# KOTLETA.net
KiCad netlist of a schematic drawn in EAGLE
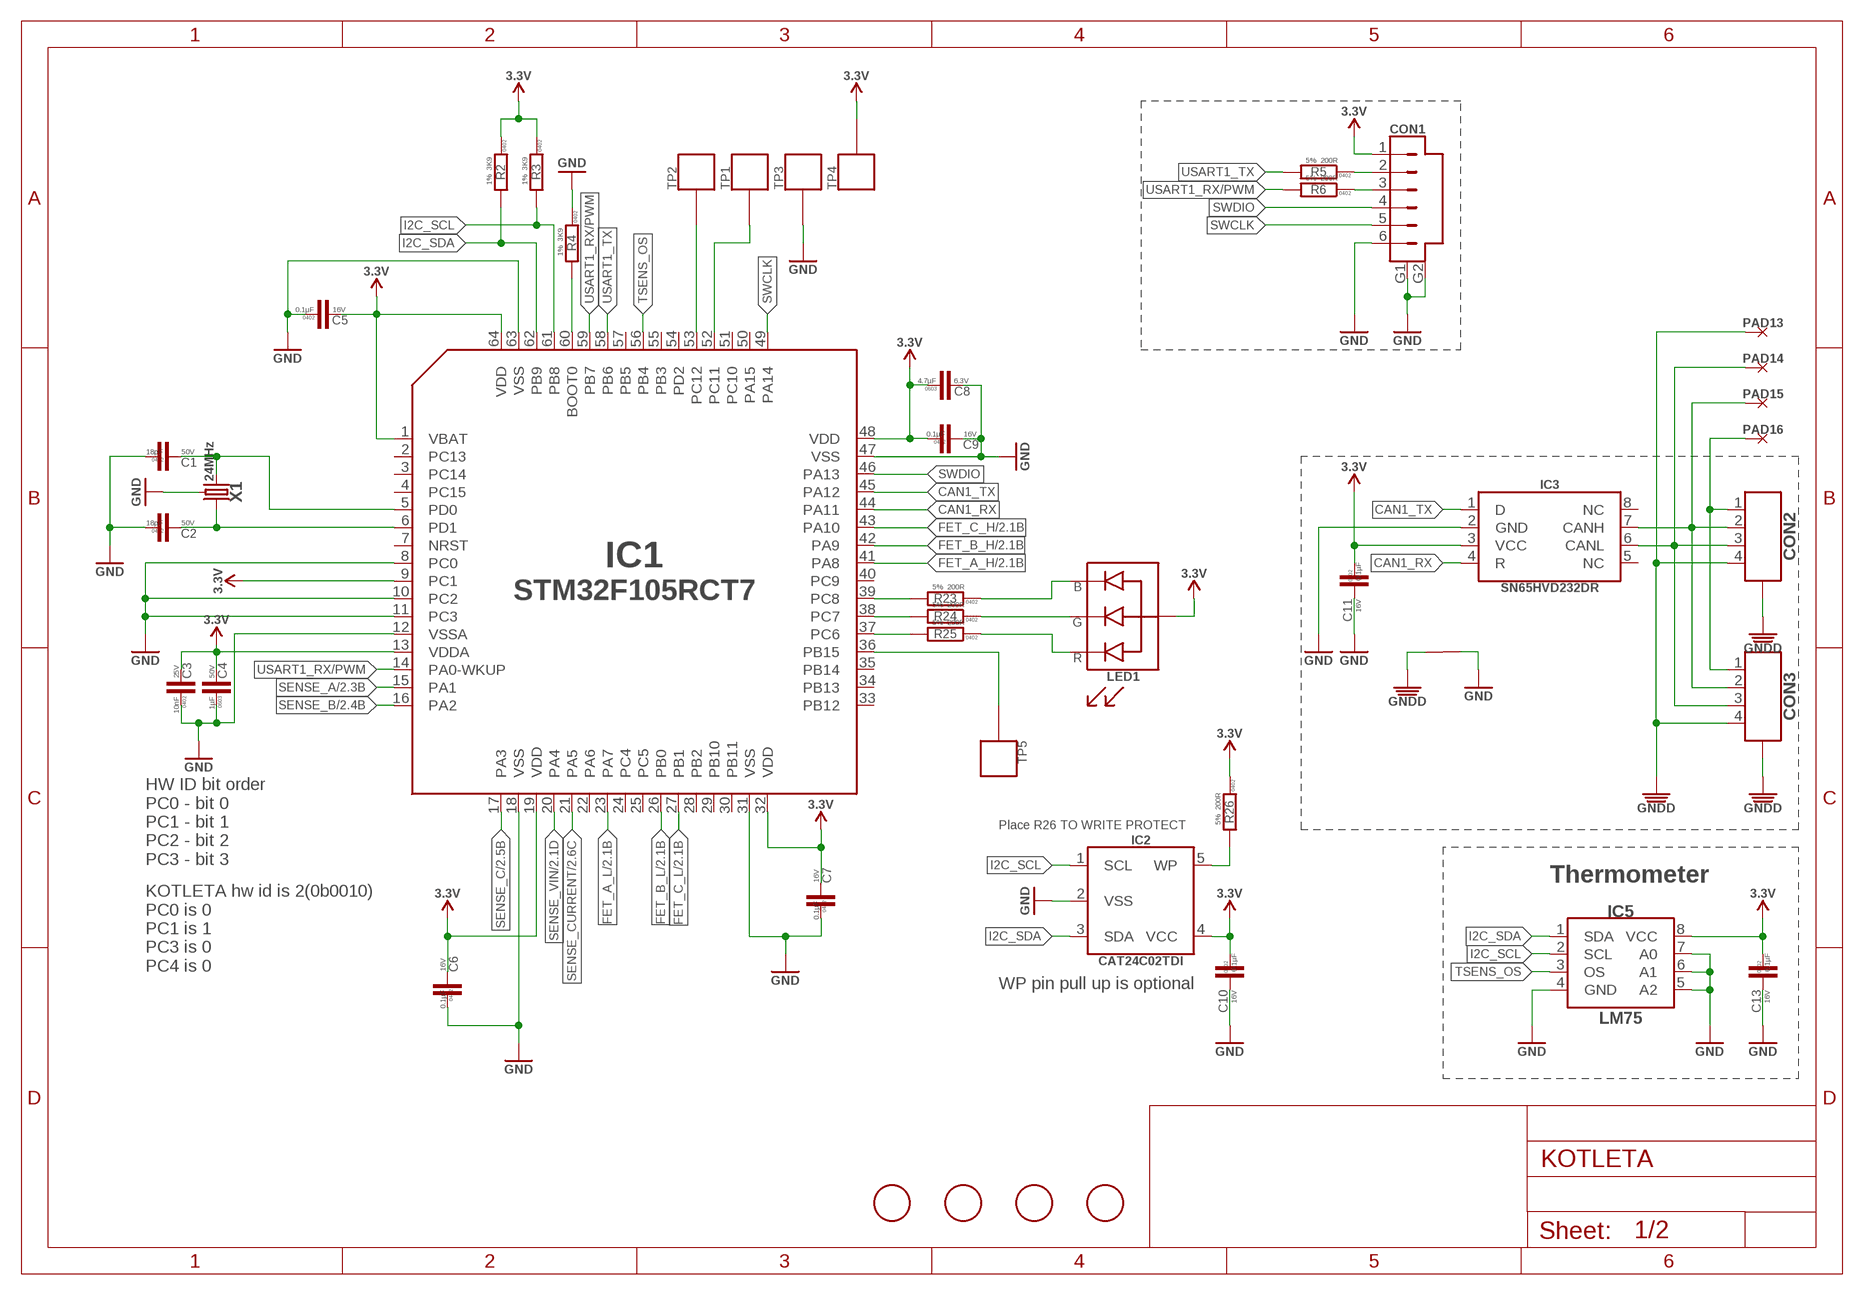
[diagram p0: schematic, sheet 1]
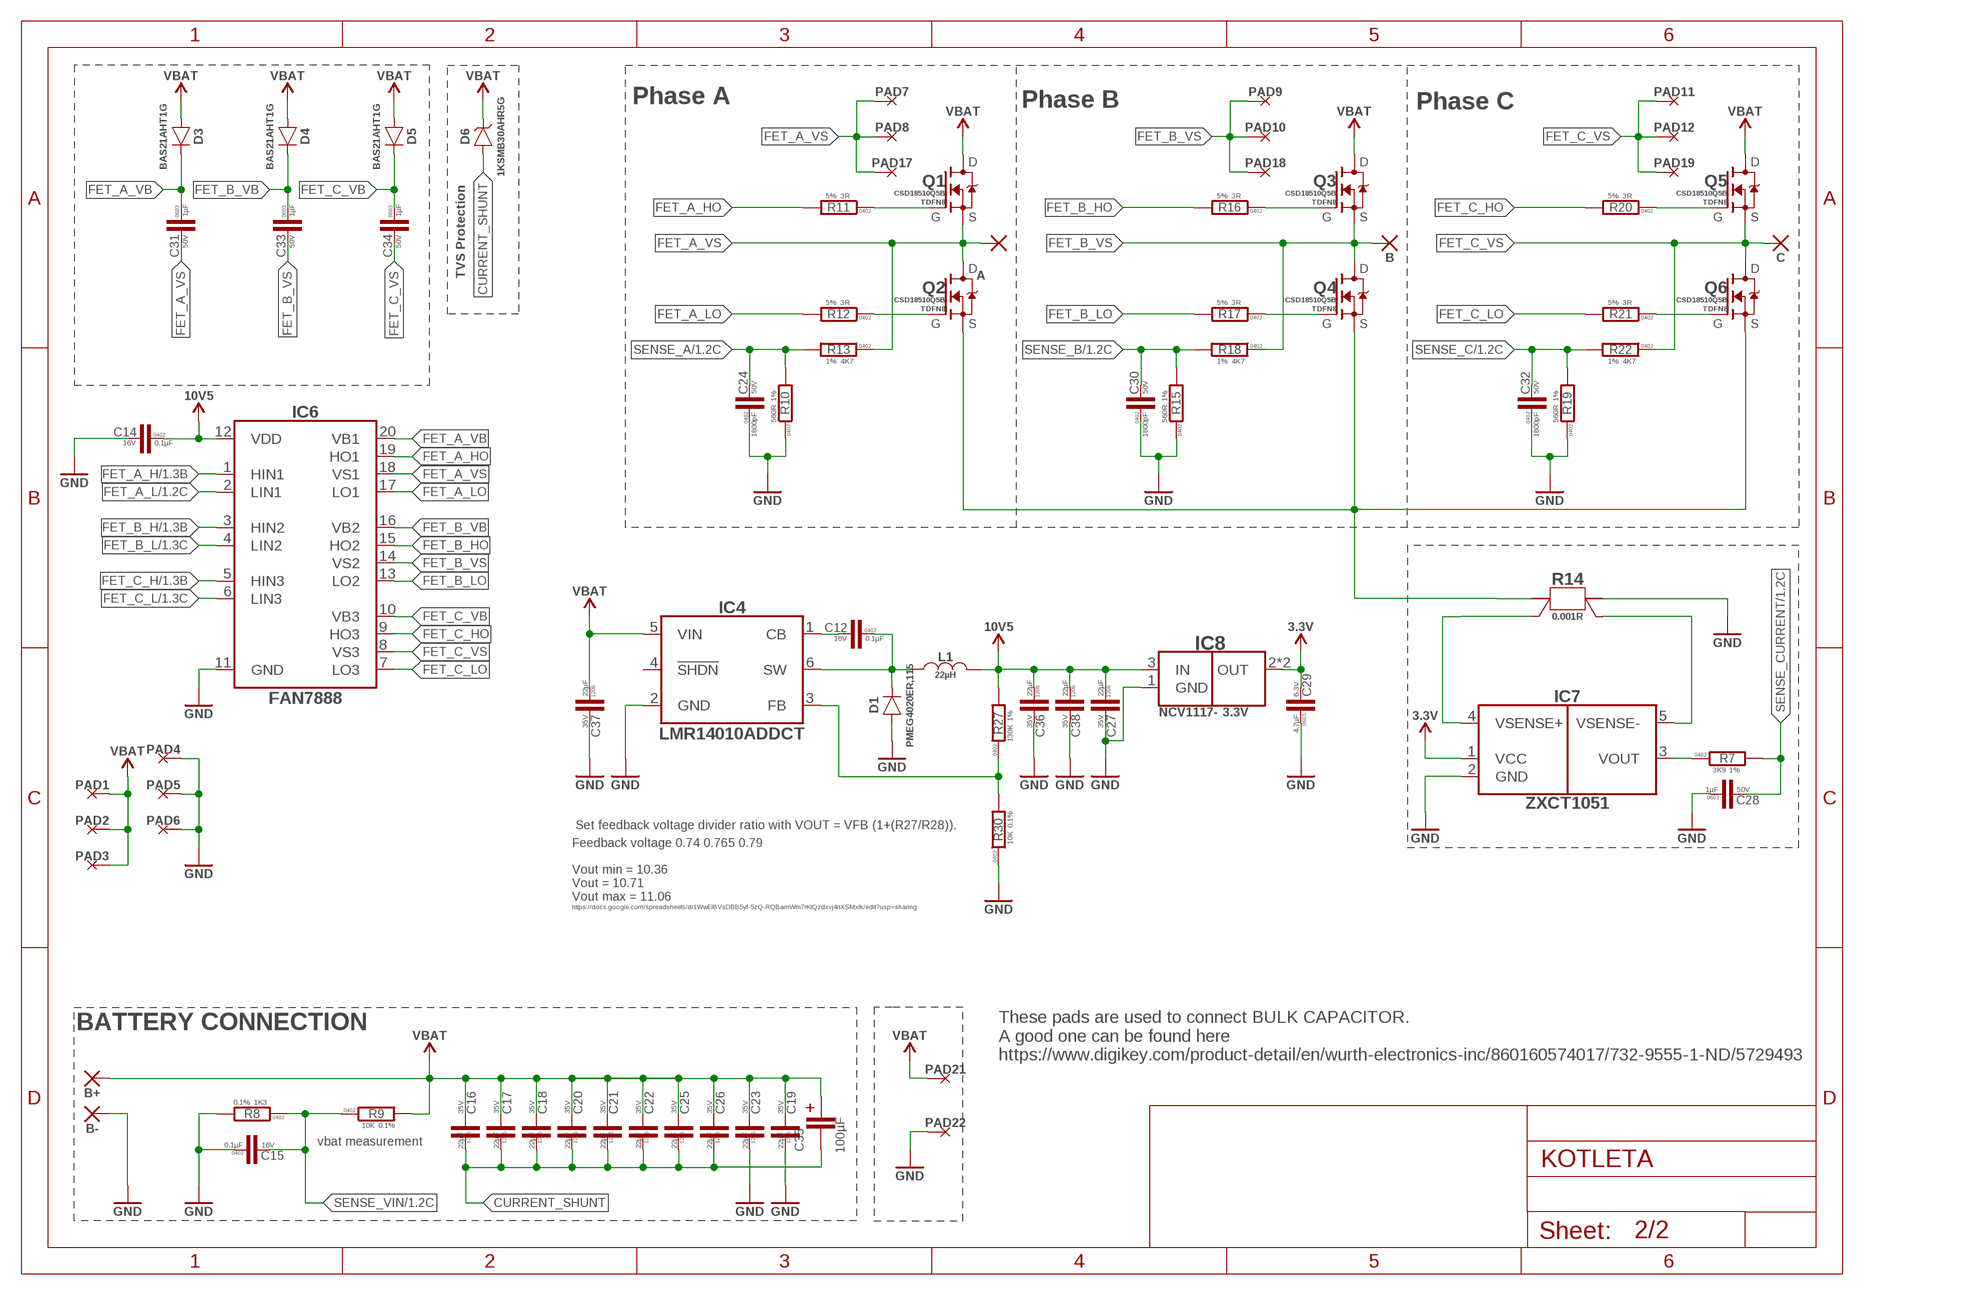
[diagram p1: schematic, sheet 2]

(export (version "E")
  (design (tool "Eeschema 10.0.6"))
  (components
    (comp (ref "C1")
      (value "18pF")
      (footprint "eagle-import:C0402")
      (fields
        (field (name "MANF") "Kemet")
        (field (name "PACKAGE") "0402")
        (field (name "TOLERANCE") "+-1%")
        (field (name "VOLTAGE") "50V")
      )
      (libsource (lib "eagle-import") (part "18PF-0402-50V_5%_NP0"))
    )
    (comp (ref "C2")
      (value "18pF")
      (footprint "eagle-import:C0402")
      (fields
        (field (name "MANF") "Kemet")
        (field (name "PACKAGE") "0402")
        (field (name "TOLERANCE") "+-1%")
        (field (name "VOLTAGE") "50V")
      )
      (libsource (lib "eagle-import") (part "18PF-0402-50V_5%_NP0"))
    )
    (comp (ref "C3")
      (value "10nF")
      (footprint "eagle-import:C0402")
      (fields
        (field (name "MANF") "Murata Electronics North America")
        (field (name "PACKAGE") "0402")
        (field (name "TOLERANCE") "+-10%")
        (field (name "VOLTAGE") "25V")
      )
      (libsource (lib "eagle-import") (part "10NF-0402-25V_10%_X7R"))
    )
    (comp (ref "C4")
      (value "1µF")
      (footprint "eagle-import:C0603")
      (fields
        (field (name "MANF") "Taiyo Yuden")
        (field (name "PACKAGE") "0603")
        (field (name "TOLERANCE") "+-10%")
        (field (name "VOLTAGE") "50V")
      )
      (libsource (lib "eagle-import") (part "1µF-0603-50V_10%_X7R"))
    )
    (comp (ref "C5")
      (value "0.1µF")
      (footprint "eagle-import:C0402")
      (fields
        (field (name "MANF") "Murata Electronics North America")
        (field (name "PACKAGE") "0402")
        (field (name "TOLERANCE") "+-10%")
        (field (name "VOLTAGE") "16V")
      )
      (libsource (lib "eagle-import") (part "0.1µF-0402-16V_10%_X7R"))
    )
    (comp (ref "C6")
      (value "0.1µF")
      (footprint "eagle-import:C0402")
      (fields
        (field (name "MANF") "Murata Electronics North America")
        (field (name "PACKAGE") "0402")
        (field (name "TOLERANCE") "+-10%")
        (field (name "VOLTAGE") "16V")
      )
      (libsource (lib "eagle-import") (part "0.1µF-0402-16V_10%_X7R"))
    )
    (comp (ref "C7")
      (value "0.1µF")
      (footprint "eagle-import:C0402")
      (fields
        (field (name "MANF") "Murata Electronics North America")
        (field (name "PACKAGE") "0402")
        (field (name "TOLERANCE") "+-10%")
        (field (name "VOLTAGE") "16V")
      )
      (libsource (lib "eagle-import") (part "0.1µF-0402-16V_10%_X7R"))
    )
    (comp (ref "C8")
      (value "4.7µF")
      (footprint "eagle-import:C0603")
      (fields
        (field (name "MANF") "Samsung Electro-Mechanics America")
        (field (name "PACKAGE") "0603")
        (field (name "TOLERANCE") "+-10%")
        (field (name "VOLTAGE") "6.3V")
      )
      (libsource (lib "eagle-import") (part "4.7µF-0603-6.3V_10%_X7R"))
    )
    (comp (ref "C9")
      (value "0.1µF")
      (footprint "eagle-import:C0402")
      (fields
        (field (name "MANF") "Murata Electronics North America")
        (field (name "PACKAGE") "0402")
        (field (name "TOLERANCE") "+-10%")
        (field (name "VOLTAGE") "16V")
      )
      (libsource (lib "eagle-import") (part "0.1µF-0402-16V_10%_X7R"))
    )
    (comp (ref "C10")
      (value "0.1µF")
      (footprint "eagle-import:C0402")
      (fields
        (field (name "MANF") "Murata Electronics North America")
        (field (name "PACKAGE") "0402")
        (field (name "TOLERANCE") "+-10%")
        (field (name "VOLTAGE") "16V")
      )
      (libsource (lib "eagle-import") (part "0.1µF-0402-16V_10%_X7R"))
    )
    (comp (ref "C11")
      (value "0.1µF")
      (footprint "eagle-import:C0402")
      (fields
        (field (name "MANF") "Murata Electronics North America")
        (field (name "PACKAGE") "0402")
        (field (name "TOLERANCE") "+-10%")
        (field (name "VOLTAGE") "16V")
      )
      (libsource (lib "eagle-import") (part "0.1µF-0402-16V_10%_X7R"))
    )
    (comp (ref "C13")
      (value "0.1µF")
      (footprint "eagle-import:C0402")
      (fields
        (field (name "MANF") "Murata Electronics North America")
        (field (name "PACKAGE") "0402")
        (field (name "TOLERANCE") "+-10%")
        (field (name "VOLTAGE") "16V")
      )
      (libsource (lib "eagle-import") (part "0.1µF-0402-16V_10%_X7R"))
    )
    (comp (ref "CON1")
      (value "CON-6P")
      (footprint "eagle-import:SM06B")
      (fields (field (name "MANF") "JST Sales America Inc") (field (name "PARTNO") "SM06B-SRSS-TB"))
      (libsource (lib "eagle-import") (part "CON-6P"))
    )
    (comp (ref "CON2")
      (value "CON-4P-JST_GH-RA")
      (footprint "eagle-import:JST_GH-4P-RA")
      (fields (field (name "MANF") "JST Sales America Inc"))
      (libsource (lib "eagle-import") (part "CON-4P-RA-JST_GH"))
    )
    (comp (ref "CON3")
      (value "CON-4P-JST_GH-RA")
      (footprint "eagle-import:JST_GH-4P-RA")
      (fields (field (name "MANF") "JST Sales America Inc"))
      (libsource (lib "eagle-import") (part "CON-4P-RA-JST_GH"))
    )
    (comp (ref "FD1")
      (value "FIDUCIALMOUNT")
      (footprint "eagle-import:FIDUCIA-MOUNT")
      (libsource (lib "eagle-import") (part "FIDUCIALMOUNT"))
    )
    (comp (ref "FD2")
      (value "FIDUCIALMOUNT")
      (footprint "eagle-import:FIDUCIA-MOUNT")
      (libsource (lib "eagle-import") (part "FIDUCIALMOUNT"))
    )
    (comp (ref "FD3")
      (value "FIDUCIALMOUNT")
      (footprint "eagle-import:FIDUCIA-MOUNT")
      (libsource (lib "eagle-import") (part "FIDUCIALMOUNT"))
    )
    (comp (ref "FD4")
      (value "FIDUCIALMOUNT")
      (footprint "eagle-import:FIDUCIA-MOUNT")
      (libsource (lib "eagle-import") (part "FIDUCIALMOUNT"))
    )
    (comp (ref "IC1")
      (value "STM32F105RCT6")
      (footprint "eagle-import:TQFP64")
      (fields
        (field (name "MANF#") "STM32F105RCT6")
        (field (name "MANF") "STMicroelectronics")
        (field (name "DIGIKEY#") "497-11547-ND")
        (field (name "MANF#_1") "STM32F105RCT7")
      )
      (libsource (lib "eagle-import") (part "STM32F105RCT6"))
    )
    (comp (ref "IC2")
      (value "CAT24C02")
      (footprint "eagle-import:SOT23-5L")
      (fields (field (name "MANF") "ON Semiconductor"))
      (libsource (lib "eagle-import") (part "CAT24C02"))
    )
    (comp (ref "IC3")
      (value "SN65HVD232D")
      (footprint "eagle-import:SOIC8")
      (fields (field (name "MANF#") "SN65HVD232DR") (field (name "MANF") "Texas Instruments"))
      (libsource (lib "eagle-import") (part "SN65HVD232D"))
    )
    (comp (ref "IC5")
      (value "LM75BD-TSSOP8")
      (footprint "eagle-import:TSSOP8")
      (fields (field (name "MANF") "NXP Semiconductors"))
      (libsource (lib "eagle-import") (part "LM75BD-TSSOP8"))
    )
    (comp (ref "LED1")
      (value "LTST-C19HE1WT")
      (footprint "eagle-import:LITE_ON_RGB_LED")
      (fields (field (name "MANF") "Lite-On Inc"))
      (libsource (lib "eagle-import") (part "LTST-C19HE1WT"))
    )
    (comp (ref "PAD13")
      (value "PAD-HOLE-0.6")
      (footprint "eagle-import:HOLE_0.6")
      (libsource (lib "eagle-import") (part "PAD-HOLE-0.6"))
    )
    (comp (ref "PAD14")
      (value "PAD-HOLE-0.6")
      (footprint "eagle-import:HOLE_0.6")
      (libsource (lib "eagle-import") (part "PAD-HOLE-0.6"))
    )
    (comp (ref "PAD15")
      (value "PAD-HOLE-0.6")
      (footprint "eagle-import:HOLE_0.6")
      (libsource (lib "eagle-import") (part "PAD-HOLE-0.6"))
    )
    (comp (ref "PAD16")
      (value "PAD-HOLE-0.6")
      (footprint "eagle-import:HOLE_0.6")
      (libsource (lib "eagle-import") (part "PAD-HOLE-0.6"))
    )
    (comp (ref "R2")
      (value "3K9")
      (footprint "eagle-import:R0402")
      (fields (field (name "MANF") "Yageo") (field (name "PACKAGE") "0402") (field (name "TOLERANCE") "1%"))
      (libsource (lib "eagle-import") (part "3K9-0402-1%"))
    )
    (comp (ref "R3")
      (value "3K9")
      (footprint "eagle-import:R0402")
      (fields (field (name "MANF") "Yageo") (field (name "PACKAGE") "0402") (field (name "TOLERANCE") "1%"))
      (libsource (lib "eagle-import") (part "3K9-0402-1%"))
    )
    (comp (ref "R4")
      (value "3K9")
      (footprint "eagle-import:R0402")
      (fields (field (name "MANF") "Yageo") (field (name "PACKAGE") "0402") (field (name "TOLERANCE") "1%"))
      (libsource (lib "eagle-import") (part "3K9-0402-1%"))
    )
    (comp (ref "R5")
      (value "200R")
      (footprint "eagle-import:R0402")
      (fields
        (field (name "MANF") "Yageo")
        (field (name "PACKAGE") "0402")
        (field (name "TOLERANCE") "5%")
        (field (name "PARTNO") "RC0402FR-07240RL")
      )
      (libsource (lib "eagle-import") (part "200R-0402-5%"))
    )
    (comp (ref "R6")
      (value "200R")
      (footprint "eagle-import:R0402")
      (fields
        (field (name "MANF") "Yageo")
        (field (name "PACKAGE") "0402")
        (field (name "TOLERANCE") "5%")
        (field (name "PARTNO") "RC0402FR-07240RL")
      )
      (libsource (lib "eagle-import") (part "200R-0402-5%"))
    )
    (comp (ref "R23")
      (value "200R")
      (footprint "eagle-import:R0402")
      (fields
        (field (name "MANF") "Yageo")
        (field (name "PACKAGE") "0402")
        (field (name "TOLERANCE") "5%")
        (field (name "PARTNO") "RC0402FR-07240RL")
      )
      (libsource (lib "eagle-import") (part "200R-0402-5%"))
    )
    (comp (ref "R24")
      (value "200R")
      (footprint "eagle-import:R0402")
      (fields
        (field (name "MANF") "Yageo")
        (field (name "PACKAGE") "0402")
        (field (name "TOLERANCE") "5%")
        (field (name "PARTNO") "RC0402FR-07240RL")
      )
      (libsource (lib "eagle-import") (part "200R-0402-5%"))
    )
    (comp (ref "R25")
      (value "200R")
      (footprint "eagle-import:R0402")
      (fields
        (field (name "MANF") "Yageo")
        (field (name "PACKAGE") "0402")
        (field (name "TOLERANCE") "5%")
        (field (name "PARTNO") "RC0402FR-07240RL")
      )
      (libsource (lib "eagle-import") (part "200R-0402-5%"))
    )
    (comp (ref "R26")
      (value "200R")
      (footprint "eagle-import:R0402")
      (fields
        (field (name "MANF") "Yageo")
        (field (name "PACKAGE") "0402")
        (field (name "TOLERANCE") "5%")
        (field (name "PARTNO") "RC0402FR-07240RL")
      )
      (libsource (lib "eagle-import") (part "200R-0402-5%"))
    )
    (comp (ref "TP1")
      (value "PAD.05")
      (footprint "eagle-import:PAD.05X.05")
      (libsource (lib "eagle-import") (part "PAD.05"))
    )
    (comp (ref "TP2")
      (value "PAD.05")
      (footprint "eagle-import:PAD.05X.05")
      (libsource (lib "eagle-import") (part "PAD.05"))
    )
    (comp (ref "TP3")
      (value "PAD.05")
      (footprint "eagle-import:PAD.05X.05")
      (libsource (lib "eagle-import") (part "PAD.05"))
    )
    (comp (ref "TP4")
      (value "PAD.05")
      (footprint "eagle-import:PAD.05X.05")
      (libsource (lib "eagle-import") (part "PAD.05"))
    )
    (comp (ref "TP5")
      (value "PAD.05")
      (footprint "eagle-import:PAD.05X.05")
      (libsource (lib "eagle-import") (part "PAD.05"))
    )
    (comp (ref "U$2")
      (value "CONNECTION")
      (footprint "eagle-import:CONNECTION")
      (libsource (lib "eagle-import") (part "CONNECTION"))
    )
    (comp (ref "X1")
      (value "24MHz")
      (footprint "eagle-import:OSCILLATOR-3.2X2.5-4P")
      (fields
        (field (name "MANF") "Kyocera International Inc. Electronic Components")
        (field (name "DIGIKEY#") "1253-1198-1-ND")
        (field (name "MANF#") "CX3225GB24000P0HPQCC")
      )
      (libsource (lib "eagle-import") (part "CRYSTAL-4P-3.2X2.5-4P-24MHZ"))
    )
    (comp (ref "A")
      (value "WIREPADSMD5-2,5")
      (footprint "eagle-import:5-2,5")
      (libsource (lib "eagle-import") (part "WIREPADSMD5-2,5"))
    )
    (comp (ref "B")
      (value "WIREPADSMD5-2,5")
      (footprint "eagle-import:5-2,5")
      (libsource (lib "eagle-import") (part "WIREPADSMD5-2,5"))
    )
    (comp (ref "B+")
      (value "WIREPADSMD5-2,5")
      (footprint "eagle-import:5-2,5")
      (libsource (lib "eagle-import") (part "WIREPADSMD5-2,5"))
    )
    (comp (ref "B-")
      (value "WIREPADSMD5-2,5")
      (footprint "eagle-import:5-2,5")
      (libsource (lib "eagle-import") (part "WIREPADSMD5-2,5"))
    )
    (comp (ref "C")
      (value "WIREPADSMD5-2,5")
      (footprint "eagle-import:5-2,5")
      (libsource (lib "eagle-import") (part "WIREPADSMD5-2,5"))
    )
    (comp (ref "C12")
      (value "0.1µF")
      (footprint "eagle-import:C0402")
      (fields
        (field (name "MANF") "Murata Electronics North America")
        (field (name "PACKAGE") "0402")
        (field (name "TOLERANCE") "+-10%")
        (field (name "VOLTAGE") "16V")
      )
      (libsource (lib "eagle-import") (part "0.1µF-0402-16V_10%_X7R"))
    )
    (comp (ref "C14")
      (value "0.1µF")
      (footprint "eagle-import:C0402")
      (fields
        (field (name "MANF") "Murata Electronics North America")
        (field (name "PACKAGE") "0402")
        (field (name "TOLERANCE") "+-10%")
        (field (name "VOLTAGE") "16V")
      )
      (libsource (lib "eagle-import") (part "0.1µF-0402-16V_10%_X7R"))
    )
    (comp (ref "C15")
      (value "0.1µF")
      (footprint "eagle-import:C0402")
      (fields
        (field (name "MANF") "Murata Electronics North America")
        (field (name "PACKAGE") "0402")
        (field (name "TOLERANCE") "+-10%")
        (field (name "VOLTAGE") "16V")
      )
      (libsource (lib "eagle-import") (part "0.1µF-0402-16V_10%_X7R"))
    )
    (comp (ref "C16")
      (value "22µF")
      (footprint "eagle-import:C1206")
      (fields
        (field (name "MANF") "TDK Corporation")
        (field (name "PACKAGE") "1206")
        (field (name "TOLERANCE") "+-20%")
        (field (name "VOLTAGE") "35V")
      )
      (libsource (lib "eagle-import") (part "22µF-1206-35V_20%_X5R"))
    )
    (comp (ref "C17")
      (value "22µF")
      (footprint "eagle-import:C1206")
      (fields
        (field (name "MANF") "TDK Corporation")
        (field (name "PACKAGE") "1206")
        (field (name "TOLERANCE") "+-20%")
        (field (name "VOLTAGE") "35V")
      )
      (libsource (lib "eagle-import") (part "22µF-1206-35V_20%_X5R"))
    )
    (comp (ref "C18")
      (value "22µF")
      (footprint "eagle-import:C1206")
      (fields
        (field (name "MANF") "TDK Corporation")
        (field (name "PACKAGE") "1206")
        (field (name "TOLERANCE") "+-20%")
        (field (name "VOLTAGE") "35V")
      )
      (libsource (lib "eagle-import") (part "22µF-1206-35V_20%_X5R"))
    )
    (comp (ref "C19")
      (value "22µF")
      (footprint "eagle-import:C1206")
      (fields
        (field (name "MANF") "TDK Corporation")
        (field (name "PACKAGE") "1206")
        (field (name "TOLERANCE") "+-20%")
        (field (name "VOLTAGE") "35V")
      )
      (libsource (lib "eagle-import") (part "22µF-1206-35V_20%_X5R"))
    )
    (comp (ref "C20")
      (value "22µF")
      (footprint "eagle-import:C1206")
      (fields
        (field (name "MANF") "TDK Corporation")
        (field (name "PACKAGE") "1206")
        (field (name "TOLERANCE") "+-20%")
        (field (name "VOLTAGE") "35V")
      )
      (libsource (lib "eagle-import") (part "22µF-1206-35V_20%_X5R"))
    )
    (comp (ref "C21")
      (value "22µF")
      (footprint "eagle-import:C1206")
      (fields
        (field (name "MANF") "TDK Corporation")
        (field (name "PACKAGE") "1206")
        (field (name "TOLERANCE") "+-20%")
        (field (name "VOLTAGE") "35V")
      )
      (libsource (lib "eagle-import") (part "22µF-1206-35V_20%_X5R"))
    )
    (comp (ref "C22")
      (value "22µF")
      (footprint "eagle-import:C1206")
      (fields
        (field (name "MANF") "TDK Corporation")
        (field (name "PACKAGE") "1206")
        (field (name "TOLERANCE") "+-20%")
        (field (name "VOLTAGE") "35V")
      )
      (libsource (lib "eagle-import") (part "22µF-1206-35V_20%_X5R"))
    )
    (comp (ref "C23")
      (value "22µF")
      (footprint "eagle-import:C1206")
      (fields
        (field (name "MANF") "TDK Corporation")
        (field (name "PACKAGE") "1206")
        (field (name "TOLERANCE") "+-20%")
        (field (name "VOLTAGE") "35V")
      )
      (libsource (lib "eagle-import") (part "22µF-1206-35V_20%_X5R"))
    )
    (comp (ref "C24")
      (value "1800pF")
      (footprint "eagle-import:C0402")
      (fields
        (field (name "MANF") "Yageo")
        (field (name "PACKAGE") "0402")
        (field (name "TOLERANCE") "±10%")
        (field (name "VOLTAGE") "50V")
      )
      (libsource (lib "eagle-import") (part "1800PF-0402-50V_10%_X7R"))
    )
    (comp (ref "C25")
      (value "22µF")
      (footprint "eagle-import:C1206")
      (fields
        (field (name "MANF") "TDK Corporation")
        (field (name "PACKAGE") "1206")
        (field (name "TOLERANCE") "+-20%")
        (field (name "VOLTAGE") "35V")
      )
      (libsource (lib "eagle-import") (part "22µF-1206-35V_20%_X5R"))
    )
    (comp (ref "C26")
      (value "22µF")
      (footprint "eagle-import:C1206")
      (fields
        (field (name "MANF") "TDK Corporation")
        (field (name "PACKAGE") "1206")
        (field (name "TOLERANCE") "+-20%")
        (field (name "VOLTAGE") "35V")
      )
      (libsource (lib "eagle-import") (part "22µF-1206-35V_20%_X5R"))
    )
    (comp (ref "C27")
      (value "22µF")
      (footprint "eagle-import:C1206")
      (fields
        (field (name "MANF") "TDK Corporation")
        (field (name "PACKAGE") "1206")
        (field (name "TOLERANCE") "+-20%")
        (field (name "VOLTAGE") "35V")
      )
      (libsource (lib "eagle-import") (part "22µF-1206-35V_20%_X5R"))
    )
    (comp (ref "C28")
      (value "1µF")
      (footprint "eagle-import:C0603")
      (fields
        (field (name "MANF") "Taiyo Yuden")
        (field (name "PACKAGE") "0603")
        (field (name "TOLERANCE") "+-10%")
        (field (name "VOLTAGE") "50V")
      )
      (libsource (lib "eagle-import") (part "1µF-0603-50V_10%_X7R"))
    )
    (comp (ref "C29")
      (value "4.7µF")
      (footprint "eagle-import:C0603")
      (fields
        (field (name "MANF") "Samsung Electro-Mechanics America")
        (field (name "PACKAGE") "0603")
        (field (name "TOLERANCE") "+-10%")
        (field (name "VOLTAGE") "6.3V")
      )
      (libsource (lib "eagle-import") (part "4.7µF-0603-6.3V_10%_X7R"))
    )
    (comp (ref "C30")
      (value "1800pF")
      (footprint "eagle-import:C0402")
      (fields
        (field (name "MANF") "Yageo")
        (field (name "PACKAGE") "0402")
        (field (name "TOLERANCE") "±10%")
        (field (name "VOLTAGE") "50V")
      )
      (libsource (lib "eagle-import") (part "1800PF-0402-50V_10%_X7R"))
    )
    (comp (ref "C31")
      (value "1µF")
      (footprint "eagle-import:C0603")
      (fields
        (field (name "MANF") "Taiyo Yuden")
        (field (name "PACKAGE") "0603")
        (field (name "TOLERANCE") "+-10%")
        (field (name "VOLTAGE") "50V")
      )
      (libsource (lib "eagle-import") (part "1µF-0603-50V_10%_X7R"))
    )
    (comp (ref "C32")
      (value "1800pF")
      (footprint "eagle-import:C0402")
      (fields
        (field (name "MANF") "Yageo")
        (field (name "PACKAGE") "0402")
        (field (name "TOLERANCE") "±10%")
        (field (name "VOLTAGE") "50V")
      )
      (libsource (lib "eagle-import") (part "1800PF-0402-50V_10%_X7R"))
    )
    (comp (ref "C33")
      (value "1µF")
      (footprint "eagle-import:C0603")
      (fields
        (field (name "MANF") "Taiyo Yuden")
        (field (name "PACKAGE") "0603")
        (field (name "TOLERANCE") "+-10%")
        (field (name "VOLTAGE") "50V")
      )
      (libsource (lib "eagle-import") (part "1µF-0603-50V_10%_X7R"))
    )
    (comp (ref "C34")
      (value "1µF")
      (footprint "eagle-import:C0603")
      (fields
        (field (name "MANF") "Taiyo Yuden")
        (field (name "PACKAGE") "0603")
        (field (name "TOLERANCE") "+-10%")
        (field (name "VOLTAGE") "50V")
      )
      (libsource (lib "eagle-import") (part "1µF-0603-50V_10%_X7R"))
    )
    (comp (ref "C35")
      (value "100µF")
      (footprint "eagle-import:3024")
      (fields (field (name "MANF") "Vishay Sprague") (field (name "VOLTAGE") "35V"))
      (libsource (lib "eagle-import") (part "C-TANT-3024"))
    )
    (comp (ref "C36")
      (value "22µF")
      (footprint "eagle-import:C1206")
      (fields
        (field (name "MANF") "TDK Corporation")
        (field (name "PACKAGE") "1206")
        (field (name "TOLERANCE") "+-20%")
        (field (name "VOLTAGE") "35V")
      )
      (libsource (lib "eagle-import") (part "22µF-1206-35V_20%_X5R"))
    )
    (comp (ref "C37")
      (value "22µF")
      (footprint "eagle-import:C1206")
      (fields
        (field (name "MANF") "TDK Corporation")
        (field (name "PACKAGE") "1206")
        (field (name "TOLERANCE") "+-20%")
        (field (name "VOLTAGE") "35V")
      )
      (libsource (lib "eagle-import") (part "22µF-1206-35V_20%_X5R"))
    )
    (comp (ref "C38")
      (value "22µF")
      (footprint "eagle-import:C1206")
      (fields
        (field (name "MANF") "TDK Corporation")
        (field (name "PACKAGE") "1206")
        (field (name "TOLERANCE") "+-20%")
        (field (name "VOLTAGE") "35V")
      )
      (libsource (lib "eagle-import") (part "22µF-1206-35V_20%_X5R"))
    )
    (comp (ref "D1")
      (value "PMEG4020")
      (footprint "eagle-import:SOD123W")
      (fields
        (field (name "MANF#") "PMEG4020ER,115")
        (field (name "MANF") "NXP Semiconductors")
        (field (name "VOLTAGE") "40V")
      )
      (libsource (lib "eagle-import") (part "PMEG4020"))
    )
    (comp (ref "D3")
      (value "BAS21AHT1G")
      (footprint "eagle-import:SOD323")
      (fields (field (name "MANF#") "BAS21AHT1G") (field (name "MANF") "ON Semiconductor"))
      (libsource (lib "eagle-import") (part "BAS21AHT1G"))
    )
    (comp (ref "D4")
      (value "BAS21AHT1G")
      (footprint "eagle-import:SOD323")
      (fields (field (name "MANF#") "BAS21AHT1G") (field (name "MANF") "ON Semiconductor"))
      (libsource (lib "eagle-import") (part "BAS21AHT1G"))
    )
    (comp (ref "D5")
      (value "BAS21AHT1G")
      (footprint "eagle-import:SOD323")
      (fields (field (name "MANF#") "BAS21AHT1G") (field (name "MANF") "ON Semiconductor"))
      (libsource (lib "eagle-import") (part "BAS21AHT1G"))
    )
    (comp (ref "D6")
      (value "1KSMB30AHR5G")
      (footprint "eagle-import:DO-214AA(SMB)")
      (fields (field (name "MANF#") "1KSMB30AHR5G") (field (name "MANF") "Taiwan Semiconductor Corporation"))
      (libsource (lib "eagle-import") (part "1KSMB30AHR5G"))
    )
    (comp (ref "IC4")
      (value "LMR14010ADDCT")
      (footprint "eagle-import:SOT23-6")
      (fields (field (name "MANF#") "LMR14010ADDCT") (field (name "MANF") "Texas Instruments"))
      (libsource (lib "eagle-import") (part "LMR14010ADDCT"))
    )
    (comp (ref "IC6")
      (value "FAN7888")
      (footprint "eagle-import:SOIC20")
      (fields (field (name "MANF") "Fairchild Semiconductor") (field (name "PARTNO") "FAN7888MX"))
      (libsource (lib "eagle-import") (part "FAN7888"))
    )
    (comp (ref "IC7")
      (value "ZXCT1051")
      (footprint "eagle-import:SOT23-5L")
      (fields (field (name "MANF") "Diodes Incorporated"))
      (libsource (lib "eagle-import") (part "ZXCT1051"))
    )
    (comp (ref "IC8")
      (value "3.3V")
      (footprint "eagle-import:SOT-223")
      (fields (field (name "MANF") "ON Semiconductor"))
      (libsource (lib "eagle-import") (part "NCV1117-3.3"))
    )
    (comp (ref "L1")
      (value "22µH")
      (footprint "eagle-import:SRN5040")
      (fields (field (name "MANF") "Bourns Inc"))
      (libsource (lib "eagle-import") (part "22µH-SRN5040-22U"))
    )
    (comp (ref "PAD1")
      (value "PAD-HOLE-0.6")
      (footprint "eagle-import:HOLE_0.6")
      (libsource (lib "eagle-import") (part "PAD-HOLE-0.6"))
    )
    (comp (ref "PAD2")
      (value "PAD-HOLE-0.6")
      (footprint "eagle-import:HOLE_0.6")
      (libsource (lib "eagle-import") (part "PAD-HOLE-0.6"))
    )
    (comp (ref "PAD3")
      (value "PAD-HOLE-0.6")
      (footprint "eagle-import:HOLE_0.6")
      (libsource (lib "eagle-import") (part "PAD-HOLE-0.6"))
    )
    (comp (ref "PAD4")
      (value "PAD-HOLE-0.6")
      (footprint "eagle-import:HOLE_0.6")
      (libsource (lib "eagle-import") (part "PAD-HOLE-0.6"))
    )
    (comp (ref "PAD5")
      (value "PAD-HOLE-0.6")
      (footprint "eagle-import:HOLE_0.6")
      (libsource (lib "eagle-import") (part "PAD-HOLE-0.6"))
    )
    (comp (ref "PAD6")
      (value "PAD-HOLE-0.6")
      (footprint "eagle-import:HOLE_0.6")
      (libsource (lib "eagle-import") (part "PAD-HOLE-0.6"))
    )
    (comp (ref "PAD7")
      (value "PAD-HOLE-0.6")
      (footprint "eagle-import:HOLE_0.6")
      (libsource (lib "eagle-import") (part "PAD-HOLE-0.6"))
    )
    (comp (ref "PAD8")
      (value "PAD-HOLE-0.6")
      (footprint "eagle-import:HOLE_0.6")
      (libsource (lib "eagle-import") (part "PAD-HOLE-0.6"))
    )
    (comp (ref "PAD9")
      (value "PAD-HOLE-0.6")
      (footprint "eagle-import:HOLE_0.6")
      (libsource (lib "eagle-import") (part "PAD-HOLE-0.6"))
    )
    (comp (ref "PAD10")
      (value "PAD-HOLE-0.6")
      (footprint "eagle-import:HOLE_0.6")
      (libsource (lib "eagle-import") (part "PAD-HOLE-0.6"))
    )
    (comp (ref "PAD11")
      (value "PAD-HOLE-0.6")
      (footprint "eagle-import:HOLE_0.6")
      (libsource (lib "eagle-import") (part "PAD-HOLE-0.6"))
    )
    (comp (ref "PAD12")
      (value "PAD-HOLE-0.6")
      (footprint "eagle-import:HOLE_0.6")
      (libsource (lib "eagle-import") (part "PAD-HOLE-0.6"))
    )
    (comp (ref "PAD17")
      (value "PAD-HOLE-0.6")
      (footprint "eagle-import:HOLE_0.6")
      (libsource (lib "eagle-import") (part "PAD-HOLE-0.6"))
    )
    (comp (ref "PAD18")
      (value "PAD-HOLE-0.6")
      (footprint "eagle-import:HOLE_0.6")
      (libsource (lib "eagle-import") (part "PAD-HOLE-0.6"))
    )
    (comp (ref "PAD19")
      (value "PAD-HOLE-0.6")
      (footprint "eagle-import:HOLE_0.6")
      (libsource (lib "eagle-import") (part "PAD-HOLE-0.6"))
    )
    (comp (ref "PAD21")
      (value "PAD-HOLE-0.8")
      (footprint "eagle-import:HOLE_0.8")
      (libsource (lib "eagle-import") (part "PAD-HOLE-0.8"))
    )
    (comp (ref "PAD22")
      (value "PAD-HOLE-0.8")
      (footprint "eagle-import:HOLE_0.8")
      (libsource (lib "eagle-import") (part "PAD-HOLE-0.8"))
    )
    (comp (ref "Q1")
      (value "CSD18510Q5B")
      (footprint "eagle-import:PG-TDSON-8")
      (fields
        (field (name "MANF#") "CSD18510Q5B")
        (field (name "PACKAGE") "TDFN8")
        (field (name "MANF") "Texas Instruments")
      )
      (libsource (lib "eagle-import") (part "CSD18510Q5B"))
    )
    (comp (ref "Q2")
      (value "CSD18510Q5B")
      (footprint "eagle-import:PG-TDSON-8")
      (fields
        (field (name "MANF#") "CSD18510Q5B")
        (field (name "PACKAGE") "TDFN8")
        (field (name "MANF") "Texas Instruments")
      )
      (libsource (lib "eagle-import") (part "CSD18510Q5B"))
    )
    (comp (ref "Q3")
      (value "CSD18510Q5B")
      (footprint "eagle-import:PG-TDSON-8")
      (fields
        (field (name "MANF#") "CSD18510Q5B")
        (field (name "PACKAGE") "TDFN8")
        (field (name "MANF") "Texas Instruments")
      )
      (libsource (lib "eagle-import") (part "CSD18510Q5B"))
    )
    (comp (ref "Q4")
      (value "CSD18510Q5B")
      (footprint "eagle-import:PG-TDSON-8")
      (fields
        (field (name "MANF#") "CSD18510Q5B")
        (field (name "PACKAGE") "TDFN8")
        (field (name "MANF") "Texas Instruments")
      )
      (libsource (lib "eagle-import") (part "CSD18510Q5B"))
    )
    (comp (ref "Q5")
      (value "CSD18510Q5B")
      (footprint "eagle-import:PG-TDSON-8")
      (fields
        (field (name "MANF#") "CSD18510Q5B")
        (field (name "PACKAGE") "TDFN8")
        (field (name "MANF") "Texas Instruments")
      )
      (libsource (lib "eagle-import") (part "CSD18510Q5B"))
    )
    (comp (ref "Q6")
      (value "CSD18510Q5B")
      (footprint "eagle-import:PG-TDSON-8")
      (fields
        (field (name "MANF#") "CSD18510Q5B")
        (field (name "PACKAGE") "TDFN8")
        (field (name "MANF") "Texas Instruments")
      )
      (libsource (lib "eagle-import") (part "CSD18510Q5B"))
    )
    (comp (ref "R7")
      (value "3K9")
      (footprint "eagle-import:R0402")
      (fields (field (name "MANF") "Yageo") (field (name "PACKAGE") "0402") (field (name "TOLERANCE") "1%"))
      (libsource (lib "eagle-import") (part "3K9-0402-1%"))
    )
    (comp (ref "R8")
      (value "1K3")
      (footprint "eagle-import:R0402")
      (fields
        (field (name "MANF") "Panasonic Electronic Components")
        (field (name "PACKAGE") "0402")
        (field (name "TOLERANCE") "0.1%")
      )
      (libsource (lib "eagle-import") (part "1K3-0402-0.1%"))
    )
    (comp (ref "R9")
      (value "10K")
      (footprint "eagle-import:R0402")
      (fields
        (field (name "MANF") "Panasonic Electronic Components")
        (field (name "PACKAGE") "0402")
        (field (name "TOLERANCE") "0.1%")
      )
      (libsource (lib "eagle-import") (part "10K-0402-0.1%"))
    )
    (comp (ref "R10")
      (value "560R")
      (footprint "eagle-import:R0402")
      (fields
        (field (name "MANF") "Vishay Dale")
        (field (name "PACKAGE") "0402")
        (field (name "TOLERANCE") "1%")
      )
      (libsource (lib "eagle-import") (part "560R-0402-1%"))
    )
    (comp (ref "R11")
      (value "3R")
      (footprint "eagle-import:R0402")
      (fields
        (field (name "MANF") "Panasonic Electronic Components")
        (field (name "PACKAGE") "0402")
        (field (name "TOLERANCE") "5%")
      )
      (libsource (lib "eagle-import") (part "3R-0402-5%"))
    )
    (comp (ref "R12")
      (value "3R")
      (footprint "eagle-import:R0402")
      (fields
        (field (name "MANF") "Panasonic Electronic Components")
        (field (name "PACKAGE") "0402")
        (field (name "TOLERANCE") "5%")
      )
      (libsource (lib "eagle-import") (part "3R-0402-5%"))
    )
    (comp (ref "R13")
      (value "4K7")
      (footprint "eagle-import:R0402")
      (fields (field (name "MANF") "Yageo") (field (name "PACKAGE") "0402") (field (name "TOLERANCE") "1%"))
      (libsource (lib "eagle-import") (part "4K7-0402-1%"))
    )
    (comp (ref "R14")
      (value "0.001R")
      (footprint "eagle-import:R2010-KELVIN")
      (fields
        (field (name "MANF") "Stackpole Electronics Inc.")
        (field (name "POWER") "1.5W")
        (field (name "TOLERANCE") "1%")
      )
      (libsource (lib "eagle-import") (part "CURRENT_SHUNT_KELVIN-2010-KELVIN-0.001R"))
    )
    (comp (ref "R15")
      (value "560R")
      (footprint "eagle-import:R0402")
      (fields
        (field (name "MANF") "Vishay Dale")
        (field (name "PACKAGE") "0402")
        (field (name "TOLERANCE") "1%")
      )
      (libsource (lib "eagle-import") (part "560R-0402-1%"))
    )
    (comp (ref "R16")
      (value "3R")
      (footprint "eagle-import:R0402")
      (fields
        (field (name "MANF") "Panasonic Electronic Components")
        (field (name "PACKAGE") "0402")
        (field (name "TOLERANCE") "5%")
      )
      (libsource (lib "eagle-import") (part "3R-0402-5%"))
    )
    (comp (ref "R17")
      (value "3R")
      (footprint "eagle-import:R0402")
      (fields
        (field (name "MANF") "Panasonic Electronic Components")
        (field (name "PACKAGE") "0402")
        (field (name "TOLERANCE") "5%")
      )
      (libsource (lib "eagle-import") (part "3R-0402-5%"))
    )
    (comp (ref "R18")
      (value "4K7")
      (footprint "eagle-import:R0402")
      (fields (field (name "MANF") "Yageo") (field (name "PACKAGE") "0402") (field (name "TOLERANCE") "1%"))
      (libsource (lib "eagle-import") (part "4K7-0402-1%"))
    )
    (comp (ref "R19")
      (value "560R")
      (footprint "eagle-import:R0402")
      (fields
        (field (name "MANF") "Vishay Dale")
        (field (name "PACKAGE") "0402")
        (field (name "TOLERANCE") "1%")
      )
      (libsource (lib "eagle-import") (part "560R-0402-1%"))
    )
    (comp (ref "R20")
      (value "3R")
      (footprint "eagle-import:R0402")
      (fields
        (field (name "MANF") "Panasonic Electronic Components")
        (field (name "PACKAGE") "0402")
        (field (name "TOLERANCE") "5%")
      )
      (libsource (lib "eagle-import") (part "3R-0402-5%"))
    )
    (comp (ref "R21")
      (value "3R")
      (footprint "eagle-import:R0402")
      (fields
        (field (name "MANF") "Panasonic Electronic Components")
        (field (name "PACKAGE") "0402")
        (field (name "TOLERANCE") "5%")
      )
      (libsource (lib "eagle-import") (part "3R-0402-5%"))
    )
    (comp (ref "R22")
      (value "4K7")
      (footprint "eagle-import:R0402")
      (fields (field (name "MANF") "Yageo") (field (name "PACKAGE") "0402") (field (name "TOLERANCE") "1%"))
      (libsource (lib "eagle-import") (part "4K7-0402-1%"))
    )
    (comp (ref "R27")
      (value "130K")
      (footprint "eagle-import:R0402")
      (fields (field (name "PACKAGE") "0402") (field (name "TOLERANCE") "1%") (field (name "MANF") "Yageo"))
      (libsource (lib "eagle-import") (part "R-0402-1%"))
    )
    (comp (ref "R30")
      (value "10K")
      (footprint "eagle-import:R0402")
      (fields
        (field (name "MANF") "Panasonic Electronic Components")
        (field (name "PACKAGE") "0402")
        (field (name "TOLERANCE") "0.1%")
      )
      (libsource (lib "eagle-import") (part "10K-0402-0.1%"))
    )
  )
  (nets
    (net (code "1") (name "CAN1_RX") (class "Default")
      (node (ref "IC1") (pin "44") (pinfunction "PA11_44") (pintype "bidirectional"))
      (node (ref "IC3") (pin "4") (pinfunction "R_4") (pintype "bidirectional"))
    )
    (net (code "2") (name "CAN1_TX") (class "Default")
      (node (ref "IC1") (pin "45") (pinfunction "PA12_45") (pintype "bidirectional"))
      (node (ref "IC3") (pin "1") (pinfunction "D_1") (pintype "bidirectional"))
    )
    (net (code "3") (name "CURRENT_SHUNT") (class "Default")
      (node (ref "C16") (pin "P$1") (pinfunction "1_P$1") (pintype "passive"))
      (node (ref "C17") (pin "P$1") (pinfunction "1_P$1") (pintype "passive"))
      (node (ref "C18") (pin "P$1") (pinfunction "1_P$1") (pintype "passive"))
      (node (ref "C20") (pin "P$1") (pinfunction "1_P$1") (pintype "passive"))
      (node (ref "C21") (pin "P$1") (pinfunction "1_P$1") (pintype "passive"))
      (node (ref "C22") (pin "P$1") (pinfunction "1_P$1") (pintype "passive"))
      (node (ref "C25") (pin "P$1") (pinfunction "1_P$1") (pintype "passive"))
      (node (ref "C26") (pin "P$1") (pinfunction "1_P$1") (pintype "passive"))
      (node (ref "C35") (pin "-") (pinfunction "-_-") (pintype "passive"))
      (node (ref "D6") (pin "A") (pinfunction "A_A") (pintype "passive"))
      (node (ref "Q2") (pin "1S") (pinfunction "S_1S") (pintype "passive"))
      (node (ref "Q2") (pin "2S") (pinfunction "S_2S") (pintype "passive"))
      (node (ref "Q2") (pin "3S") (pinfunction "S_3S") (pintype "passive"))
      (node (ref "Q4") (pin "1S") (pinfunction "S_1S") (pintype "passive"))
      (node (ref "Q4") (pin "2S") (pinfunction "S_2S") (pintype "passive"))
      (node (ref "Q4") (pin "3S") (pinfunction "S_3S") (pintype "passive"))
      (node (ref "Q6") (pin "1S") (pinfunction "S_1S") (pintype "passive"))
      (node (ref "Q6") (pin "2S") (pinfunction "S_2S") (pintype "passive"))
      (node (ref "Q6") (pin "3S") (pinfunction "S_3S") (pintype "passive"))
      (node (ref "R14") (pin "1") (pinfunction "1_1") (pintype "bidirectional"))
      (node (ref "R14") (pin "11") (pinfunction "1_11") (pintype "bidirectional"))
    )
    (net (code "4") (name "FET_A_H") (class "Default")
      (node (ref "IC1") (pin "41") (pinfunction "PA8_41") (pintype "bidirectional"))
      (node (ref "IC6") (pin "1") (pinfunction "HIN1_1") (pintype "bidirectional"))
    )
    (net (code "5") (name "FET_A_HO") (class "Default")
      (node (ref "IC6") (pin "19") (pinfunction "HO1_19") (pintype "bidirectional"))
      (node (ref "R11") (pin "2") (pinfunction "2_2") (pintype "passive"))
    )
    (net (code "6") (name "FET_A_L") (class "Default")
      (node (ref "IC1") (pin "23") (pinfunction "PA7_23") (pintype "bidirectional"))
      (node (ref "IC6") (pin "2") (pinfunction "LIN1_2") (pintype "bidirectional"))
    )
    (net (code "7") (name "FET_A_LO") (class "Default")
      (node (ref "IC6") (pin "17") (pinfunction "LO1_17") (pintype "bidirectional"))
      (node (ref "R12") (pin "2") (pinfunction "2_2") (pintype "passive"))
    )
    (net (code "8") (name "FET_A_VB") (class "Default")
      (node (ref "C31") (pin "P$1") (pinfunction "1_P$1") (pintype "passive"))
      (node (ref "D3") (pin "C") (pinfunction "C_C") (pintype "passive"))
      (node (ref "IC6") (pin "20") (pinfunction "VB1_20") (pintype "bidirectional"))
    )
    (net (code "9") (name "FET_A_VS") (class "Default")
      (node (ref "A") (pin "1") (pinfunction "P_1") (pintype "passive"))
      (node (ref "C31") (pin "P$2") (pinfunction "2_P$2") (pintype "passive"))
      (node (ref "IC6") (pin "18") (pinfunction "VS1_18") (pintype "bidirectional"))
      (node (ref "PAD17") (pin "P$1") (pinfunction "P$1_P$1") (pintype "bidirectional"))
      (node (ref "PAD7") (pin "P$1") (pinfunction "P$1_P$1") (pintype "bidirectional"))
      (node (ref "PAD8") (pin "P$1") (pinfunction "P$1_P$1") (pintype "bidirectional"))
      (node (ref "Q1") (pin "1S") (pinfunction "S_1S") (pintype "passive"))
      (node (ref "Q1") (pin "2S") (pinfunction "S_2S") (pintype "passive"))
      (node (ref "Q1") (pin "3S") (pinfunction "S_3S") (pintype "passive"))
      (node (ref "Q2") (pin "5D") (pinfunction "D_5D") (pintype "passive"))
      (node (ref "Q2") (pin "6D") (pinfunction "D_6D") (pintype "passive"))
      (node (ref "Q2") (pin "7D") (pinfunction "D_7D") (pintype "passive"))
      (node (ref "Q2") (pin "8D") (pinfunction "D_8D") (pintype "passive"))
      (node (ref "Q2") (pin "PAD_D") (pinfunction "D_PAD_D") (pintype "passive"))
      (node (ref "R13") (pin "1") (pinfunction "1_1") (pintype "passive"))
    )
    (net (code "10") (name "FET_B_H") (class "Default")
      (node (ref "IC1") (pin "42") (pinfunction "PA9_42") (pintype "bidirectional"))
      (node (ref "IC6") (pin "3") (pinfunction "HIN2_3") (pintype "bidirectional"))
    )
    (net (code "11") (name "FET_B_HO") (class "Default")
      (node (ref "IC6") (pin "15") (pinfunction "HO2_15") (pintype "bidirectional"))
      (node (ref "R16") (pin "2") (pinfunction "2_2") (pintype "passive"))
    )
    (net (code "12") (name "FET_B_L") (class "Default")
      (node (ref "IC1") (pin "26") (pinfunction "PB0_26") (pintype "bidirectional"))
      (node (ref "IC6") (pin "4") (pinfunction "LIN2_4") (pintype "bidirectional"))
    )
    (net (code "13") (name "FET_B_LO") (class "Default")
      (node (ref "IC6") (pin "13") (pinfunction "LO2_13") (pintype "bidirectional"))
      (node (ref "R17") (pin "2") (pinfunction "2_2") (pintype "passive"))
    )
    (net (code "14") (name "FET_B_VB") (class "Default")
      (node (ref "C33") (pin "P$1") (pinfunction "1_P$1") (pintype "passive"))
      (node (ref "D4") (pin "C") (pinfunction "C_C") (pintype "passive"))
      (node (ref "IC6") (pin "16") (pinfunction "VB2_16") (pintype "bidirectional"))
    )
    (net (code "15") (name "FET_B_VS") (class "Default")
      (node (ref "B") (pin "1") (pinfunction "P_1") (pintype "passive"))
      (node (ref "C33") (pin "P$2") (pinfunction "2_P$2") (pintype "passive"))
      (node (ref "IC6") (pin "14") (pinfunction "VS2_14") (pintype "bidirectional"))
      (node (ref "PAD10") (pin "P$1") (pinfunction "P$1_P$1") (pintype "bidirectional"))
      (node (ref "PAD18") (pin "P$1") (pinfunction "P$1_P$1") (pintype "bidirectional"))
      (node (ref "PAD9") (pin "P$1") (pinfunction "P$1_P$1") (pintype "bidirectional"))
      (node (ref "Q3") (pin "1S") (pinfunction "S_1S") (pintype "passive"))
      (node (ref "Q3") (pin "2S") (pinfunction "S_2S") (pintype "passive"))
      (node (ref "Q3") (pin "3S") (pinfunction "S_3S") (pintype "passive"))
      (node (ref "Q4") (pin "5D") (pinfunction "D_5D") (pintype "passive"))
      (node (ref "Q4") (pin "6D") (pinfunction "D_6D") (pintype "passive"))
      (node (ref "Q4") (pin "7D") (pinfunction "D_7D") (pintype "passive"))
      (node (ref "Q4") (pin "8D") (pinfunction "D_8D") (pintype "passive"))
      (node (ref "Q4") (pin "PAD_D") (pinfunction "D_PAD_D") (pintype "passive"))
      (node (ref "R18") (pin "1") (pinfunction "1_1") (pintype "passive"))
    )
    (net (code "16") (name "FET_C_H") (class "Default")
      (node (ref "IC1") (pin "43") (pinfunction "PA10_43") (pintype "bidirectional"))
      (node (ref "IC6") (pin "5") (pinfunction "HIN3_5") (pintype "bidirectional"))
    )
    (net (code "17") (name "FET_C_HO") (class "Default")
      (node (ref "IC6") (pin "9") (pinfunction "HO3_9") (pintype "bidirectional"))
      (node (ref "R20") (pin "2") (pinfunction "2_2") (pintype "passive"))
    )
    (net (code "18") (name "FET_C_L") (class "Default")
      (node (ref "IC1") (pin "27") (pinfunction "PB1_27") (pintype "bidirectional"))
      (node (ref "IC6") (pin "6") (pinfunction "LIN3_6") (pintype "bidirectional"))
    )
    (net (code "19") (name "FET_C_LO") (class "Default")
      (node (ref "IC6") (pin "7") (pinfunction "LO3_7") (pintype "bidirectional"))
      (node (ref "R21") (pin "2") (pinfunction "2_2") (pintype "passive"))
    )
    (net (code "20") (name "FET_C_VB") (class "Default")
      (node (ref "C34") (pin "P$1") (pinfunction "1_P$1") (pintype "passive"))
      (node (ref "D5") (pin "C") (pinfunction "C_C") (pintype "passive"))
      (node (ref "IC6") (pin "10") (pinfunction "VB3_10") (pintype "bidirectional"))
    )
    (net (code "21") (name "FET_C_VS") (class "Default")
      (node (ref "C") (pin "1") (pinfunction "P_1") (pintype "passive"))
      (node (ref "C34") (pin "P$2") (pinfunction "2_P$2") (pintype "passive"))
      (node (ref "IC6") (pin "8") (pinfunction "VS3_8") (pintype "bidirectional"))
      (node (ref "PAD11") (pin "P$1") (pinfunction "P$1_P$1") (pintype "bidirectional"))
      (node (ref "PAD12") (pin "P$1") (pinfunction "P$1_P$1") (pintype "bidirectional"))
      (node (ref "PAD19") (pin "P$1") (pinfunction "P$1_P$1") (pintype "bidirectional"))
      (node (ref "Q5") (pin "1S") (pinfunction "S_1S") (pintype "passive"))
      (node (ref "Q5") (pin "2S") (pinfunction "S_2S") (pintype "passive"))
      (node (ref "Q5") (pin "3S") (pinfunction "S_3S") (pintype "passive"))
      (node (ref "Q6") (pin "5D") (pinfunction "D_5D") (pintype "passive"))
      (node (ref "Q6") (pin "6D") (pinfunction "D_6D") (pintype "passive"))
      (node (ref "Q6") (pin "7D") (pinfunction "D_7D") (pintype "passive"))
      (node (ref "Q6") (pin "8D") (pinfunction "D_8D") (pintype "passive"))
      (node (ref "Q6") (pin "PAD_D") (pinfunction "D_PAD_D") (pintype "passive"))
      (node (ref "R22") (pin "1") (pinfunction "1_1") (pintype "passive"))
    )
    (net (code "22") (name "GND") (class "Default")
      (node (ref "B-") (pin "1") (pinfunction "P_1") (pintype "passive"))
      (node (ref "C1") (pin "1") (pinfunction "1_1") (pintype "passive"))
      (node (ref "C10") (pin "2") (pinfunction "2_2") (pintype "passive"))
      (node (ref "C11") (pin "2") (pinfunction "2_2") (pintype "passive"))
      (node (ref "C13") (pin "2") (pinfunction "2_2") (pintype "passive"))
      (node (ref "C14") (pin "2") (pinfunction "2_2") (pintype "passive"))
      (node (ref "C15") (pin "1") (pinfunction "1_1") (pintype "passive"))
      (node (ref "C19") (pin "P$1") (pinfunction "1_P$1") (pintype "passive"))
      (node (ref "C2") (pin "1") (pinfunction "1_1") (pintype "passive"))
      (node (ref "C23") (pin "P$1") (pinfunction "1_P$1") (pintype "passive"))
      (node (ref "C24") (pin "1") (pinfunction "1_1") (pintype "passive"))
      (node (ref "C27") (pin "P$2") (pinfunction "2_P$2") (pintype "passive"))
      (node (ref "C28") (pin "P$1") (pinfunction "1_P$1") (pintype "passive"))
      (node (ref "C29") (pin "P$1") (pinfunction "1_P$1") (pintype "passive"))
      (node (ref "C3") (pin "1") (pinfunction "1_1") (pintype "passive"))
      (node (ref "C30") (pin "1") (pinfunction "1_1") (pintype "passive"))
      (node (ref "C32") (pin "1") (pinfunction "1_1") (pintype "passive"))
      (node (ref "C36") (pin "P$2") (pinfunction "2_P$2") (pintype "passive"))
      (node (ref "C37") (pin "P$2") (pinfunction "2_P$2") (pintype "passive"))
      (node (ref "C38") (pin "P$2") (pinfunction "2_P$2") (pintype "passive"))
      (node (ref "C4") (pin "P$1") (pinfunction "1_P$1") (pintype "passive"))
      (node (ref "C5") (pin "1") (pinfunction "1_1") (pintype "passive"))
      (node (ref "C6") (pin "1") (pinfunction "1_1") (pintype "passive"))
      (node (ref "C7") (pin "1") (pinfunction "1_1") (pintype "passive"))
      (node (ref "C8") (pin "P$2") (pinfunction "2_P$2") (pintype "passive"))
      (node (ref "C9") (pin "2") (pinfunction "2_2") (pintype "passive"))
      (node (ref "CON1") (pin "6") (pinfunction "6_6") (pintype "passive"))
      (node (ref "CON1") (pin "G1") (pinfunction "G1_G1") (pintype "passive"))
      (node (ref "CON1") (pin "G2") (pinfunction "G2_G2") (pintype "passive"))
      (node (ref "D1") (pin "A") (pinfunction "A_A") (pintype "passive"))
      (node (ref "IC1") (pin "10") (pinfunction "PC2_10") (pintype "bidirectional"))
      (node (ref "IC1") (pin "11") (pinfunction "PC3_11") (pintype "bidirectional"))
      (node (ref "IC1") (pin "12") (pinfunction "VSSA_12") (pintype "bidirectional"))
      (node (ref "IC1") (pin "18") (pinfunction "VSS_18") (pintype "bidirectional"))
      (node (ref "IC1") (pin "31") (pinfunction "VSS_31") (pintype "bidirectional"))
      (node (ref "IC1") (pin "47") (pinfunction "VSS_47") (pintype "bidirectional"))
      (node (ref "IC1") (pin "63") (pinfunction "VSS_63") (pintype "bidirectional"))
      (node (ref "IC1") (pin "8") (pinfunction "PC0_8") (pintype "bidirectional"))
      (node (ref "IC2") (pin "2") (pinfunction "VSS_2") (pintype "bidirectional"))
      (node (ref "IC3") (pin "2") (pinfunction "GND_2") (pintype "bidirectional"))
      (node (ref "IC4") (pin "2") (pinfunction "GND_2") (pintype "bidirectional"))
      (node (ref "IC5") (pin "4") (pinfunction "GND_4") (pintype "bidirectional"))
      (node (ref "IC5") (pin "5") (pinfunction "A2_5") (pintype "bidirectional"))
      (node (ref "IC5") (pin "6") (pinfunction "A1_6") (pintype "bidirectional"))
      (node (ref "IC5") (pin "7") (pinfunction "A0_7") (pintype "bidirectional"))
      (node (ref "IC6") (pin "11") (pinfunction "GND_11") (pintype "bidirectional"))
      (node (ref "IC7") (pin "2") (pinfunction "GND_2") (pintype "bidirectional"))
      (node (ref "IC8") (pin "1") (pinfunction "GND_1") (pintype "bidirectional"))
      (node (ref "PAD22") (pin "P$1") (pinfunction "P$1_P$1") (pintype "bidirectional"))
      (node (ref "PAD4") (pin "P$1") (pinfunction "P$1_P$1") (pintype "bidirectional"))
      (node (ref "PAD5") (pin "P$1") (pinfunction "P$1_P$1") (pintype "bidirectional"))
      (node (ref "PAD6") (pin "P$1") (pinfunction "P$1_P$1") (pintype "bidirectional"))
      (node (ref "R10") (pin "1") (pinfunction "1_1") (pintype "passive"))
      (node (ref "R14") (pin "2") (pinfunction "2_2") (pintype "bidirectional"))
      (node (ref "R14") (pin "22") (pinfunction "2_22") (pintype "bidirectional"))
      (node (ref "R15") (pin "1") (pinfunction "1_1") (pintype "passive"))
      (node (ref "R19") (pin "1") (pinfunction "1_1") (pintype "passive"))
      (node (ref "R30") (pin "1") (pinfunction "1_1") (pintype "passive"))
      (node (ref "R4") (pin "1") (pinfunction "1_1") (pintype "passive"))
      (node (ref "R8") (pin "2") (pinfunction "2_2") (pintype "passive"))
      (node (ref "TP3") (pin "P$1") (pinfunction "P$1_P$1") (pintype "passive"))
      (node (ref "U$2") (pin "P$2") (pinfunction "P$2_P$2") (pintype "bidirectional"))
      (node (ref "X1") (pin "2") (pinfunction "GND_2") (pintype "bidirectional"))
      (node (ref "X1") (pin "4") (pinfunction "GND_4") (pintype "bidirectional"))
    )
    (net (code "23") (name "GNDD") (class "Default")
      (node (ref "CON2") (pin "4") (pinfunction "4_4") (pintype "bidirectional"))
      (node (ref "CON2") (pin "M$0") (pinfunction "GND_M$0") (pintype "bidirectional"))
      (node (ref "CON2") (pin "M$1") (pinfunction "GND_M$1") (pintype "bidirectional"))
      (node (ref "CON3") (pin "4") (pinfunction "4_4") (pintype "bidirectional"))
      (node (ref "CON3") (pin "M$0") (pinfunction "GND_M$0") (pintype "bidirectional"))
      (node (ref "CON3") (pin "M$1") (pinfunction "GND_M$1") (pintype "bidirectional"))
      (node (ref "PAD13") (pin "P$1") (pinfunction "P$1_P$1") (pintype "bidirectional"))
      (node (ref "U$2") (pin "P$1") (pinfunction "P$1_P$1") (pintype "bidirectional"))
    )
    (net (code "24") (name "I2C_SCL") (class "Default")
      (node (ref "IC1") (pin "61") (pinfunction "PB8_61") (pintype "bidirectional"))
      (node (ref "IC2") (pin "1") (pinfunction "SCL_1") (pintype "bidirectional"))
      (node (ref "IC5") (pin "2") (pinfunction "SCL_2") (pintype "bidirectional"))
      (node (ref "R3") (pin "2") (pinfunction "2_2") (pintype "passive"))
    )
    (net (code "25") (name "I2C_SDA") (class "Default")
      (node (ref "IC1") (pin "62") (pinfunction "PB9_62") (pintype "bidirectional"))
      (node (ref "IC2") (pin "3") (pinfunction "SDA_3") (pintype "bidirectional"))
      (node (ref "IC5") (pin "1") (pinfunction "SDA_1") (pintype "bidirectional"))
      (node (ref "R2") (pin "2") (pinfunction "2_2") (pintype "passive"))
    )
    (net (code "26") (name "Net-(CON1-Pad2)") (class "Default")
      (node (ref "CON1") (pin "2") (pinfunction "2_2") (pintype "passive"))
      (node (ref "R5") (pin "1") (pinfunction "1_1") (pintype "passive"))
    )
    (net (code "27") (name "Net-(CON1-Pad3)") (class "Default")
      (node (ref "CON1") (pin "3") (pinfunction "3_3") (pintype "passive"))
      (node (ref "R6") (pin "1") (pinfunction "1_1") (pintype "passive"))
    )
    (net (code "28") (name "Net-(CON2-Pad1)") (class "Default")
      (node (ref "CON2") (pin "1") (pinfunction "1_1") (pintype "bidirectional"))
      (node (ref "CON3") (pin "1") (pinfunction "1_1") (pintype "bidirectional"))
      (node (ref "PAD16") (pin "P$1") (pinfunction "P$1_P$1") (pintype "bidirectional"))
    )
    (net (code "29") (name "Net-(IC1-BOOT0)") (class "Default")
      (node (ref "IC1") (pin "60") (pinfunction "BOOT0_60") (pintype "bidirectional"))
      (node (ref "R4") (pin "2") (pinfunction "2_2") (pintype "passive"))
    )
    (net (code "30") (name "Net-(IC1-PB15)") (class "Default")
      (node (ref "IC1") (pin "36") (pinfunction "PB15_36") (pintype "bidirectional"))
      (node (ref "TP5") (pin "P$1") (pinfunction "P$1_P$1") (pintype "passive"))
    )
    (net (code "31") (name "Net-(IC1-PC6)") (class "Default")
      (node (ref "IC1") (pin "37") (pinfunction "PC6_37") (pintype "bidirectional"))
      (node (ref "R25") (pin "2") (pinfunction "2_2") (pintype "passive"))
    )
    (net (code "32") (name "Net-(IC1-PC7)") (class "Default")
      (node (ref "IC1") (pin "38") (pinfunction "PC7_38") (pintype "bidirectional"))
      (node (ref "R24") (pin "2") (pinfunction "2_2") (pintype "passive"))
    )
    (net (code "33") (name "Net-(IC1-PC8)") (class "Default")
      (node (ref "IC1") (pin "39") (pinfunction "PC8_39") (pintype "bidirectional"))
      (node (ref "R23") (pin "2") (pinfunction "2_2") (pintype "passive"))
    )
    (net (code "34") (name "Net-(IC1-PC11)") (class "Default")
      (node (ref "IC1") (pin "52") (pinfunction "PC11_52") (pintype "bidirectional"))
      (node (ref "TP1") (pin "P$1") (pinfunction "P$1_P$1") (pintype "passive"))
    )
    (net (code "35") (name "Net-(IC1-PC12)") (class "Default")
      (node (ref "IC1") (pin "53") (pinfunction "PC12_53") (pintype "bidirectional"))
      (node (ref "TP2") (pin "P$1") (pinfunction "P$1_P$1") (pintype "passive"))
    )
    (net (code "36") (name "Net-(IC1-PD0)") (class "Default")
      (node (ref "C1") (pin "2") (pinfunction "2_2") (pintype "passive"))
      (node (ref "IC1") (pin "5") (pinfunction "PD0_5") (pintype "bidirectional"))
      (node (ref "X1") (pin "3") (pinfunction "2_3") (pintype "passive"))
    )
    (net (code "37") (name "Net-(IC1-PD1)") (class "Default")
      (node (ref "C2") (pin "2") (pinfunction "2_2") (pintype "passive"))
      (node (ref "IC1") (pin "6") (pinfunction "PD1_6") (pintype "bidirectional"))
      (node (ref "X1") (pin "1") (pinfunction "1_1") (pintype "passive"))
    )
    (net (code "38") (name "Net-(IC2-WP)") (class "Default")
      (node (ref "IC2") (pin "5") (pinfunction "WP_5") (pintype "bidirectional"))
      (node (ref "R26") (pin "2") (pinfunction "2_2") (pintype "passive"))
    )
    (net (code "39") (name "Net-(IC3-CANH)") (class "Default")
      (node (ref "CON2") (pin "2") (pinfunction "2_2") (pintype "bidirectional"))
      (node (ref "CON3") (pin "2") (pinfunction "2_2") (pintype "bidirectional"))
      (node (ref "IC3") (pin "7") (pinfunction "CANH_7") (pintype "bidirectional"))
      (node (ref "PAD15") (pin "P$1") (pinfunction "P$1_P$1") (pintype "bidirectional"))
    )
    (net (code "40") (name "Net-(IC3-CANL)") (class "Default")
      (node (ref "CON2") (pin "3") (pinfunction "3_3") (pintype "bidirectional"))
      (node (ref "CON3") (pin "3") (pinfunction "3_3") (pintype "bidirectional"))
      (node (ref "IC3") (pin "6") (pinfunction "CANL_6") (pintype "bidirectional"))
      (node (ref "PAD14") (pin "P$1") (pinfunction "P$1_P$1") (pintype "bidirectional"))
    )
    (net (code "41") (name "Net-(IC4-CB)") (class "Default")
      (node (ref "C12") (pin "2") (pinfunction "2_2") (pintype "passive"))
      (node (ref "IC4") (pin "1") (pinfunction "CB_1") (pintype "bidirectional"))
    )
    (net (code "42") (name "Net-(IC4-FB)") (class "Default")
      (node (ref "IC4") (pin "3") (pinfunction "FB_3") (pintype "bidirectional"))
      (node (ref "R27") (pin "1") (pinfunction "1_1") (pintype "passive"))
      (node (ref "R30") (pin "2") (pinfunction "2_2") (pintype "passive"))
    )
    (net (code "43") (name "Net-(IC4-SW)") (class "Default")
      (node (ref "C12") (pin "1") (pinfunction "1_1") (pintype "passive"))
      (node (ref "D1") (pin "C") (pinfunction "C_C") (pintype "passive"))
      (node (ref "IC4") (pin "6") (pinfunction "SW_6") (pintype "bidirectional"))
      (node (ref "L1") (pin "P$1") (pinfunction "P$1_P$1") (pintype "bidirectional"))
    )
    (net (code "44") (name "Net-(IC7-VOUT)") (class "Default")
      (node (ref "IC7") (pin "3") (pinfunction "VOUT_3") (pintype "bidirectional"))
      (node (ref "R7") (pin "1") (pinfunction "1_1") (pintype "passive"))
    )
    (net (code "45") (name "Net-(IC7-VSENSE+)") (class "Default")
      (node (ref "IC7") (pin "4") (pinfunction "VSENSE+_4") (pintype "bidirectional"))
      (node (ref "R14") (pin "S1") (pinfunction "S1_S1") (pintype "bidirectional"))
    )
    (net (code "46") (name "Net-(IC7-VSENSE-)") (class "Default")
      (node (ref "IC7") (pin "5") (pinfunction "VSENSE-_5") (pintype "bidirectional"))
      (node (ref "R14") (pin "S2") (pinfunction "S2_S2") (pintype "bidirectional"))
    )
    (net (code "47") (name "Net-(LED1-PadB)") (class "Default")
      (node (ref "LED1") (pin "B") (pinfunction "B_B") (pintype "bidirectional"))
      (node (ref "R23") (pin "1") (pinfunction "1_1") (pintype "passive"))
    )
    (net (code "48") (name "Net-(LED1-PadG)") (class "Default")
      (node (ref "LED1") (pin "G") (pinfunction "G_G") (pintype "bidirectional"))
      (node (ref "R24") (pin "1") (pinfunction "1_1") (pintype "passive"))
    )
    (net (code "49") (name "Net-(LED1-PadR)") (class "Default")
      (node (ref "LED1") (pin "R") (pinfunction "R_R") (pintype "bidirectional"))
      (node (ref "R25") (pin "1") (pinfunction "1_1") (pintype "passive"))
    )
    (net (code "50") (name "Net-(Q1-G)") (class "Default")
      (node (ref "Q1") (pin "4G") (pinfunction "G_4G") (pintype "passive"))
      (node (ref "R11") (pin "1") (pinfunction "1_1") (pintype "passive"))
    )
    (net (code "51") (name "Net-(Q2-G)") (class "Default")
      (node (ref "Q2") (pin "4G") (pinfunction "G_4G") (pintype "passive"))
      (node (ref "R12") (pin "1") (pinfunction "1_1") (pintype "passive"))
    )
    (net (code "52") (name "Net-(Q3-G)") (class "Default")
      (node (ref "Q3") (pin "4G") (pinfunction "G_4G") (pintype "passive"))
      (node (ref "R16") (pin "1") (pinfunction "1_1") (pintype "passive"))
    )
    (net (code "53") (name "Net-(Q4-G)") (class "Default")
      (node (ref "Q4") (pin "4G") (pinfunction "G_4G") (pintype "passive"))
      (node (ref "R17") (pin "1") (pinfunction "1_1") (pintype "passive"))
    )
    (net (code "54") (name "Net-(Q5-G)") (class "Default")
      (node (ref "Q5") (pin "4G") (pinfunction "G_4G") (pintype "passive"))
      (node (ref "R20") (pin "1") (pinfunction "1_1") (pintype "passive"))
    )
    (net (code "55") (name "Net-(Q6-G)") (class "Default")
      (node (ref "Q6") (pin "4G") (pinfunction "G_4G") (pintype "passive"))
      (node (ref "R21") (pin "1") (pinfunction "1_1") (pintype "passive"))
    )
    (net (code "56") (name "SENSE_A") (class "Default")
      (node (ref "C24") (pin "2") (pinfunction "2_2") (pintype "passive"))
      (node (ref "IC1") (pin "15") (pinfunction "PA1_15") (pintype "bidirectional"))
      (node (ref "R10") (pin "2") (pinfunction "2_2") (pintype "passive"))
      (node (ref "R13") (pin "2") (pinfunction "2_2") (pintype "passive"))
    )
    (net (code "57") (name "SENSE_B") (class "Default")
      (node (ref "C30") (pin "2") (pinfunction "2_2") (pintype "passive"))
      (node (ref "IC1") (pin "16") (pinfunction "PA2_16") (pintype "bidirectional"))
      (node (ref "R15") (pin "2") (pinfunction "2_2") (pintype "passive"))
      (node (ref "R18") (pin "2") (pinfunction "2_2") (pintype "passive"))
    )
    (net (code "58") (name "SENSE_C") (class "Default")
      (node (ref "C32") (pin "2") (pinfunction "2_2") (pintype "passive"))
      (node (ref "IC1") (pin "17") (pinfunction "PA3_17") (pintype "bidirectional"))
      (node (ref "R19") (pin "2") (pinfunction "2_2") (pintype "passive"))
      (node (ref "R22") (pin "2") (pinfunction "2_2") (pintype "passive"))
    )
    (net (code "59") (name "SENSE_CURRENT") (class "Default")
      (node (ref "C28") (pin "P$2") (pinfunction "2_P$2") (pintype "passive"))
      (node (ref "IC1") (pin "21") (pinfunction "PA5_21") (pintype "bidirectional"))
      (node (ref "R7") (pin "2") (pinfunction "2_2") (pintype "passive"))
    )
    (net (code "60") (name "SENSE_VIN") (class "Default")
      (node (ref "C15") (pin "2") (pinfunction "2_2") (pintype "passive"))
      (node (ref "IC1") (pin "20") (pinfunction "PA4_20") (pintype "bidirectional"))
      (node (ref "R8") (pin "1") (pinfunction "1_1") (pintype "passive"))
      (node (ref "R9") (pin "1") (pinfunction "1_1") (pintype "passive"))
    )
    (net (code "61") (name "SWCLK") (class "Default")
      (node (ref "CON1") (pin "5") (pinfunction "5_5") (pintype "passive"))
      (node (ref "IC1") (pin "49") (pinfunction "PA14_49") (pintype "bidirectional"))
    )
    (net (code "62") (name "SWDIO") (class "Default")
      (node (ref "CON1") (pin "4") (pinfunction "4_4") (pintype "passive"))
      (node (ref "IC1") (pin "46") (pinfunction "PA13_46") (pintype "bidirectional"))
    )
    (net (code "63") (name "TSENS_OS") (class "Default")
      (node (ref "IC1") (pin "56") (pinfunction "PB4_56") (pintype "bidirectional"))
      (node (ref "IC5") (pin "3") (pinfunction "OS_3") (pintype "bidirectional"))
    )
    (net (code "64") (name "USART1_RX{slash}PWM") (class "Default")
      (node (ref "IC1") (pin "14") (pinfunction "PA0-WKUP_14") (pintype "bidirectional"))
      (node (ref "IC1") (pin "59") (pinfunction "PB7_59") (pintype "bidirectional"))
      (node (ref "R6") (pin "2") (pinfunction "2_2") (pintype "passive"))
    )
    (net (code "65") (name "USART1_TX") (class "Default")
      (node (ref "IC1") (pin "58") (pinfunction "PB6_58") (pintype "bidirectional"))
      (node (ref "R5") (pin "2") (pinfunction "2_2") (pintype "passive"))
    )
    (net (code "66") (name "VBAT") (class "Default")
      (node (ref "B+") (pin "1") (pinfunction "P_1") (pintype "passive"))
      (node (ref "C16") (pin "P$2") (pinfunction "2_P$2") (pintype "passive"))
      (node (ref "C17") (pin "P$2") (pinfunction "2_P$2") (pintype "passive"))
      (node (ref "C18") (pin "P$2") (pinfunction "2_P$2") (pintype "passive"))
      (node (ref "C19") (pin "P$2") (pinfunction "2_P$2") (pintype "passive"))
      (node (ref "C20") (pin "P$2") (pinfunction "2_P$2") (pintype "passive"))
      (node (ref "C21") (pin "P$2") (pinfunction "2_P$2") (pintype "passive"))
      (node (ref "C22") (pin "P$2") (pinfunction "2_P$2") (pintype "passive"))
      (node (ref "C23") (pin "P$2") (pinfunction "2_P$2") (pintype "passive"))
      (node (ref "C25") (pin "P$2") (pinfunction "2_P$2") (pintype "passive"))
      (node (ref "C26") (pin "P$2") (pinfunction "2_P$2") (pintype "passive"))
      (node (ref "C35") (pin "+") (pinfunction "+_+") (pintype "passive"))
      (node (ref "C37") (pin "P$1") (pinfunction "1_P$1") (pintype "passive"))
      (node (ref "D3") (pin "A") (pinfunction "A_A") (pintype "passive"))
      (node (ref "D4") (pin "A") (pinfunction "A_A") (pintype "passive"))
      (node (ref "D5") (pin "A") (pinfunction "A_A") (pintype "passive"))
      (node (ref "D6") (pin "C") (pinfunction "C_C") (pintype "passive"))
      (node (ref "IC4") (pin "5") (pinfunction "VIN_5") (pintype "bidirectional"))
      (node (ref "PAD1") (pin "P$1") (pinfunction "P$1_P$1") (pintype "bidirectional"))
      (node (ref "PAD2") (pin "P$1") (pinfunction "P$1_P$1") (pintype "bidirectional"))
      (node (ref "PAD21") (pin "P$1") (pinfunction "P$1_P$1") (pintype "bidirectional"))
      (node (ref "PAD3") (pin "P$1") (pinfunction "P$1_P$1") (pintype "bidirectional"))
      (node (ref "Q1") (pin "5D") (pinfunction "D_5D") (pintype "passive"))
      (node (ref "Q1") (pin "6D") (pinfunction "D_6D") (pintype "passive"))
      (node (ref "Q1") (pin "7D") (pinfunction "D_7D") (pintype "passive"))
      (node (ref "Q1") (pin "8D") (pinfunction "D_8D") (pintype "passive"))
      (node (ref "Q1") (pin "PAD_D") (pinfunction "D_PAD_D") (pintype "passive"))
      (node (ref "Q3") (pin "5D") (pinfunction "D_5D") (pintype "passive"))
      (node (ref "Q3") (pin "6D") (pinfunction "D_6D") (pintype "passive"))
      (node (ref "Q3") (pin "7D") (pinfunction "D_7D") (pintype "passive"))
      (node (ref "Q3") (pin "8D") (pinfunction "D_8D") (pintype "passive"))
      (node (ref "Q3") (pin "PAD_D") (pinfunction "D_PAD_D") (pintype "passive"))
      (node (ref "Q5") (pin "5D") (pinfunction "D_5D") (pintype "passive"))
      (node (ref "Q5") (pin "6D") (pinfunction "D_6D") (pintype "passive"))
      (node (ref "Q5") (pin "7D") (pinfunction "D_7D") (pintype "passive"))
      (node (ref "Q5") (pin "8D") (pinfunction "D_8D") (pintype "passive"))
      (node (ref "Q5") (pin "PAD_D") (pinfunction "D_PAD_D") (pintype "passive"))
      (node (ref "R9") (pin "2") (pinfunction "2_2") (pintype "passive"))
    )
    (net (code "67") (name "VDD_3V3") (class "Default")
      (node (ref "C10") (pin "1") (pinfunction "1_1") (pintype "passive"))
      (node (ref "C11") (pin "1") (pinfunction "1_1") (pintype "passive"))
      (node (ref "C13") (pin "1") (pinfunction "1_1") (pintype "passive"))
      (node (ref "C29") (pin "P$2") (pinfunction "2_P$2") (pintype "passive"))
      (node (ref "C3") (pin "2") (pinfunction "2_2") (pintype "passive"))
      (node (ref "C4") (pin "P$2") (pinfunction "2_P$2") (pintype "passive"))
      (node (ref "C5") (pin "2") (pinfunction "2_2") (pintype "passive"))
      (node (ref "C6") (pin "2") (pinfunction "2_2") (pintype "passive"))
      (node (ref "C7") (pin "2") (pinfunction "2_2") (pintype "passive"))
      (node (ref "C8") (pin "P$1") (pinfunction "1_P$1") (pintype "passive"))
      (node (ref "C9") (pin "1") (pinfunction "1_1") (pintype "passive"))
      (node (ref "CON1") (pin "1") (pinfunction "1_1") (pintype "passive"))
      (node (ref "IC1") (pin "1") (pinfunction "VBAT_1") (pintype "bidirectional"))
      (node (ref "IC1") (pin "13") (pinfunction "VDDA_13") (pintype "bidirectional"))
      (node (ref "IC1") (pin "19") (pinfunction "VDD_19") (pintype "bidirectional"))
      (node (ref "IC1") (pin "32") (pinfunction "VDD_32") (pintype "bidirectional"))
      (node (ref "IC1") (pin "48") (pinfunction "VDD_48") (pintype "bidirectional"))
      (node (ref "IC1") (pin "64") (pinfunction "VDD_64") (pintype "bidirectional"))
      (node (ref "IC1") (pin "9") (pinfunction "PC1_9") (pintype "bidirectional"))
      (node (ref "IC2") (pin "4") (pinfunction "VCC_4") (pintype "bidirectional"))
      (node (ref "IC3") (pin "3") (pinfunction "VCC_3") (pintype "bidirectional"))
      (node (ref "IC5") (pin "8") (pinfunction "VCC_8") (pintype "bidirectional"))
      (node (ref "IC7") (pin "1") (pinfunction "VCC_1") (pintype "bidirectional"))
      (node (ref "IC8") (pin "2") (pinfunction "OUT_2") (pintype "bidirectional"))
      (node (ref "IC8") (pin "4") (pinfunction "OUT_4") (pintype "bidirectional"))
      (node (ref "LED1") (pin "+") (pinfunction "A_+") (pintype "bidirectional"))
      (node (ref "R2") (pin "1") (pinfunction "1_1") (pintype "passive"))
      (node (ref "R26") (pin "1") (pinfunction "1_1") (pintype "passive"))
      (node (ref "R3") (pin "1") (pinfunction "1_1") (pintype "passive"))
      (node (ref "TP4") (pin "P$1") (pinfunction "P$1_P$1") (pintype "passive"))
    )
    (net (code "68") (name "VDD_10V5") (class "Default")
      (node (ref "C14") (pin "1") (pinfunction "1_1") (pintype "passive"))
      (node (ref "C27") (pin "P$1") (pinfunction "1_P$1") (pintype "passive"))
      (node (ref "C36") (pin "P$1") (pinfunction "1_P$1") (pintype "passive"))
      (node (ref "C38") (pin "P$1") (pinfunction "1_P$1") (pintype "passive"))
      (node (ref "IC6") (pin "12") (pinfunction "VDD_12") (pintype "bidirectional"))
      (node (ref "IC8") (pin "3") (pinfunction "IN_3") (pintype "bidirectional"))
      (node (ref "L1") (pin "P$2") (pinfunction "P$2_P$2") (pintype "bidirectional"))
      (node (ref "R27") (pin "2") (pinfunction "2_2") (pintype "passive"))
    )
    (net (code "69") (name "unconnected-(IC1-NRST-Pad7)") (class "Default")
      (node (ref "IC1") (pin "7") (pinfunction "NRST_7") (pintype "bidirectional"))
    )
    (net (code "70") (name "unconnected-(IC1-PA6-Pad22)") (class "Default")
      (node (ref "IC1") (pin "22") (pinfunction "PA6_22") (pintype "bidirectional"))
    )
    (net (code "71") (name "unconnected-(IC1-PA15-Pad50)") (class "Default")
      (node (ref "IC1") (pin "50") (pinfunction "PA15_50") (pintype "bidirectional"))
    )
    (net (code "72") (name "unconnected-(IC1-PB2-Pad28)") (class "Default")
      (node (ref "IC1") (pin "28") (pinfunction "PB2_28") (pintype "bidirectional"))
    )
    (net (code "73") (name "unconnected-(IC1-PB3-Pad55)") (class "Default")
      (node (ref "IC1") (pin "55") (pinfunction "PB3_55") (pintype "bidirectional"))
    )
    (net (code "74") (name "unconnected-(IC1-PB5-Pad57)") (class "Default")
      (node (ref "IC1") (pin "57") (pinfunction "PB5_57") (pintype "bidirectional"))
    )
    (net (code "75") (name "unconnected-(IC1-PB10-Pad29)") (class "Default")
      (node (ref "IC1") (pin "29") (pinfunction "PB10_29") (pintype "bidirectional"))
    )
    (net (code "76") (name "unconnected-(IC1-PB11-Pad30)") (class "Default")
      (node (ref "IC1") (pin "30") (pinfunction "PB11_30") (pintype "bidirectional"))
    )
    (net (code "77") (name "unconnected-(IC1-PB12-Pad33)") (class "Default")
      (node (ref "IC1") (pin "33") (pinfunction "PB12_33") (pintype "bidirectional"))
    )
    (net (code "78") (name "unconnected-(IC1-PB13-Pad34)") (class "Default")
      (node (ref "IC1") (pin "34") (pinfunction "PB13_34") (pintype "bidirectional"))
    )
    (net (code "79") (name "unconnected-(IC1-PB14-Pad35)") (class "Default")
      (node (ref "IC1") (pin "35") (pinfunction "PB14_35") (pintype "bidirectional"))
    )
    (net (code "80") (name "unconnected-(IC1-PC4-Pad24)") (class "Default")
      (node (ref "IC1") (pin "24") (pinfunction "PC4_24") (pintype "bidirectional"))
    )
    (net (code "81") (name "unconnected-(IC1-PC5-Pad25)") (class "Default")
      (node (ref "IC1") (pin "25") (pinfunction "PC5_25") (pintype "bidirectional"))
    )
    (net (code "82") (name "unconnected-(IC1-PC9-Pad40)") (class "Default")
      (node (ref "IC1") (pin "40") (pinfunction "PC9_40") (pintype "bidirectional"))
    )
    (net (code "83") (name "unconnected-(IC1-PC10-Pad51)") (class "Default")
      (node (ref "IC1") (pin "51") (pinfunction "PC10_51") (pintype "bidirectional"))
    )
    (net (code "84") (name "unconnected-(IC1-PC13-Pad2)") (class "Default")
      (node (ref "IC1") (pin "2") (pinfunction "PC13_2") (pintype "bidirectional"))
    )
    (net (code "85") (name "unconnected-(IC1-PC14-Pad3)") (class "Default")
      (node (ref "IC1") (pin "3") (pinfunction "PC14_3") (pintype "bidirectional"))
    )
    (net (code "86") (name "unconnected-(IC1-PC15-Pad4)") (class "Default")
      (node (ref "IC1") (pin "4") (pinfunction "PC15_4") (pintype "bidirectional"))
    )
    (net (code "87") (name "unconnected-(IC1-PD2-Pad54)") (class "Default")
      (node (ref "IC1") (pin "54") (pinfunction "PD2_54") (pintype "bidirectional"))
    )
    (net (code "88") (name "unconnected-(IC3-NC-Pad5)") (class "Default")
      (node (ref "IC3") (pin "5") (pinfunction "NC_5") (pintype "bidirectional"))
    )
    (net (code "89") (name "unconnected-(IC3-NC-Pad8)") (class "Default")
      (node (ref "IC3") (pin "8") (pinfunction "NC_8") (pintype "bidirectional"))
    )
    (net (code "90") (name "unconnected-(IC4-~{SHDN}-Pad4)") (class "Default")
      (node (ref "IC4") (pin "4") (pinfunction "~{SHDN}_4") (pintype "bidirectional"))
    )
  )
)
